# Offboard.net
KiCad netlist of a schematic drawn in Altium Designer
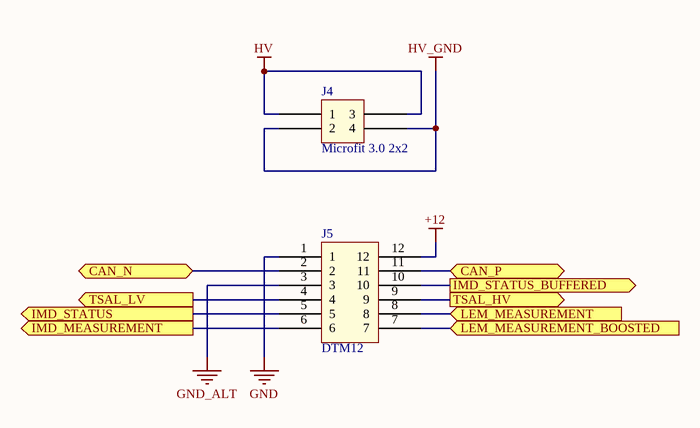
[diagram p0: Offboard.SchDoc]

(export (version "E")
  (design (tool "Eeschema 10.0.6"))
  (components
    (comp (ref "J4")
      (value "Microfit 3.0 2x2")
      (footprint "Microfit_2X2_R_TH")
      (libsource (lib "QUTMS_Microfit") (part "Microfit_2x2"))
    )
    (comp (ref "J5")
      (value "DTM12")
      (footprint "DTM13-12PA")
      (libsource (lib "QUTMS_DeutschPCB") (part "DTM12"))
    )
  )
  (nets
    (net (code "1") (name "+12") (class "Default")
      (node (ref "J5") (pin "12") (pinfunction "12_12") (pintype "passive"))
    )
    (net (code "2") (name "/CAN_N") (class "Default")
      (node (ref "J5") (pin "2") (pinfunction "2_2") (pintype "passive"))
    )
    (net (code "3") (name "/CAN_P") (class "Default")
      (node (ref "J5") (pin "11") (pinfunction "11_11") (pintype "passive"))
    )
    (net (code "4") (name "/IMD_MEASUREMENT") (class "Default")
      (node (ref "J5") (pin "6") (pinfunction "6_6") (pintype "passive"))
    )
    (net (code "5") (name "/IMD_STATUS") (class "Default")
      (node (ref "J5") (pin "5") (pinfunction "5_5") (pintype "passive"))
    )
    (net (code "6") (name "/IMD_STATUS_BUFFERED") (class "Default")
      (node (ref "J5") (pin "10") (pinfunction "10_10") (pintype "passive"))
    )
    (net (code "7") (name "/LEM_MEASUREMENT") (class "Default")
      (node (ref "J5") (pin "8") (pinfunction "8_8") (pintype "passive"))
    )
    (net (code "8") (name "/LEM_MEASUREMENT_BOOSTED") (class "Default")
      (node (ref "J5") (pin "7") (pinfunction "7_7") (pintype "passive"))
    )
    (net (code "9") (name "/TSAL_HV") (class "Default")
      (node (ref "J5") (pin "9") (pinfunction "9_9") (pintype "passive"))
    )
    (net (code "10") (name "/TSAL_LV") (class "Default")
      (node (ref "J5") (pin "4") (pinfunction "4_4") (pintype "passive"))
    )
    (net (code "11") (name "GND") (class "Default")
      (node (ref "J5") (pin "1") (pinfunction "1_1") (pintype "passive"))
    )
    (net (code "12") (name "GND_ALT") (class "Default")
      (node (ref "J5") (pin "3") (pinfunction "3_3") (pintype "passive"))
    )
    (net (code "13") (name "HV") (class "Default")
      (node (ref "J4") (pin "1") (pinfunction "1_1") (pintype "passive"))
      (node (ref "J4") (pin "3") (pinfunction "3_3") (pintype "passive"))
    )
    (net (code "14") (name "HV_GND") (class "Default")
      (node (ref "J4") (pin "2") (pinfunction "2_2") (pintype "passive"))
      (node (ref "J4") (pin "4") (pinfunction "4_4") (pintype "passive"))
    )
  )
)
